# Misc.net
KiCad netlist of a schematic drawn in Altium Designer
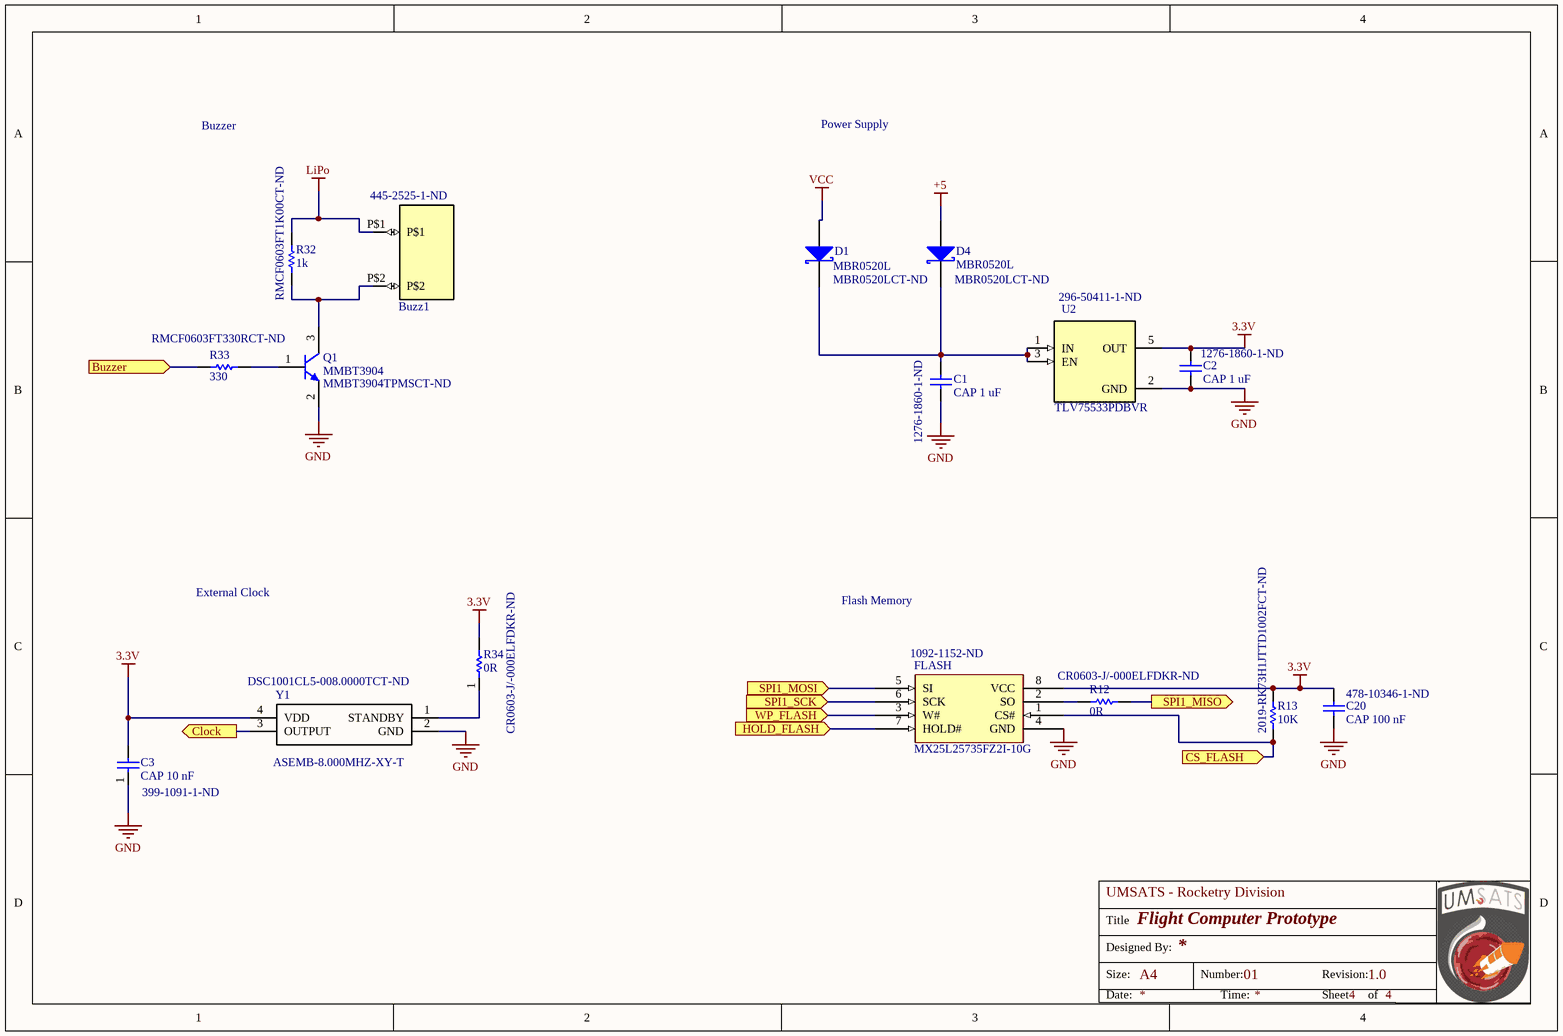
[diagram p0: Misc.SchDoc]

(export (version "E")
  (design (tool "Eeschema 10.0.6"))
  (components
    (comp (ref "Buzz1")
      (value "PS1240P02BT")
      (footprint "*PS1240P02BT_PS1240P02BT(Primary)")
      (description "Audio Buzzer Piezo 30Vo-p 3Vo-p 70dBA Pin Through Hole T/R")
      (fields (field (name "MF") "TDK") (field (name "SUPPLIER PART NUMBER 1") "445-2525-1-ND"))
      (libsource (lib "PS1240P02BT") (part "PS1240P02BT"))
    )
    (comp (ref "C1")
      (value "CAP 1 uF")
      (footprint "CL10A105KB8NNNC")
      (description "Capacitor")
      (fields
        (field (name "SUPPLIER PART NUMBER 1") "1276-1860-1-ND")
        (field (name "PUBLISHER") "Altium Limited")
      )
      (libsource (lib "Miscellaneous Devices") (part "Cap"))
    )
    (comp (ref "C2")
      (value "CAP 1 uF")
      (footprint "CL10A105KB8NNNC")
      (description "Capacitor")
      (fields
        (field (name "SUPPLIER PART NUMBER 1") "1276-1860-1-ND")
        (field (name "PUBLISHER") "Altium Limited")
      )
      (libsource (lib "Miscellaneous Devices") (part "Cap"))
    )
    (comp (ref "C3")
      (value "CAP 10 nF")
      (footprint "06035C104KAT4A")
      (description "Capacitor")
      (fields
        (field (name "SUPPLIER PART NUMBER 1") "399-1091-1-ND")
        (field (name "PUBLISHER") "Altium Limited")
      )
      (libsource (lib "") (part "Cap_1"))
    )
    (comp (ref "C20")
      (value "CAP 100 nF")
      (footprint "06035C104KAT4A")
      (description "Capacitor")
      (fields
        (field (name "SUPPLIER PART NUMBER 1") "478-10346-1-ND")
        (field (name "PUBLISHER") "Altium Limited")
      )
      (libsource (lib "Miscellaneous Devices") (part "Cap"))
    )
    (comp (ref "D1")
      (value "MBR0520L")
      (footprint "ON_Semi_CASE_425_0")
      (description "Schottky Diode")
      (fields
        (field (name "MANUFACTURER") "ON Semiconductor / Fairchild")
        (field (name "SUPPLIER PART NUMBER 1") "MBR0520LCT-ND")
      )
      (libsource (lib "MBR0520L") (part "MBR0520L"))
    )
    (comp (ref "D4")
      (value "MBR0520L")
      (footprint "ON_Semi_CASE_425_0")
      (description "Schottky Diode")
      (fields
        (field (name "MANUFACTURER") "ON Semiconductor / Fairchild")
        (field (name "SUPPLIER PART NUMBER 1") "MBR0520LCT-ND")
      )
      (libsource (lib "MBR0520L") (part "MBR0520L"))
    )
    (comp (ref "FLASH")
      (value "MX25L25735FZ2I-10G")
      (footprint "MX25L25735F:SON127P800X80_HS-9N")
      (description "MX25L25735F 256 Mb Flash Memory")
      (fields (field (name "SUPPLIER PART NUMBER 1") "1092-1152-ND"))
      (libsource (lib "S25FL064P_FlashMemory") (part "S25FL064P"))
    )
    (comp (ref "Q1")
      (value "MMBT3904")
      (footprint "FAIR-SOT23-3_V")
      (description "NPN General Purpose Amplifier, 40 V, 0.2 A, -55 to 150 degC, 3-Pin SOT23, RoHS, Tape and Reel")
      (fields (field (name "TOLERANCE") "30ppm") (field (name "SUPPLIER PART NUMBER 1") "MMBT3904TPMSCT-ND"))
      (libsource (lib "Altium Content Vault") (part "BJT-NPN-BEC-3"))
    )
    (comp (ref "R12")
      (value "0R")
      (footprint "CR0603-J/-000ELF")
      (description "Resistor")
      (fields
        (field (name "SUPPLIER PART NUMBER 1") "CR0603-J/-000ELFDKR-ND")
        (field (name "PUBLISHER") "Altium Limited")
      )
      (libsource (lib "Miscellaneous Devices") (part "Res1"))
    )
    (comp (ref "R13")
      (value "10K")
      (footprint "RK73H1JTTD1002F")
      (description "Resistor")
      (fields
        (field (name "SUPPLIER PART NUMBER 1") "2019-RK73H1JTTD1002FCT-ND")
        (field (name "PUBLISHER") "Altium Limited")
      )
      (libsource (lib "Miscellaneous Devices") (part "Res1"))
    )
    (comp (ref "R32")
      (value "1k")
      (footprint "CR0603-J/-000ELF")
      (description "Resistor")
      (fields
        (field (name "SUPPLIER PART NUMBER 1") "RMCF0603FT1K00CT-ND")
        (field (name "PUBLISHER") "Altium Limited")
      )
      (libsource (lib "Miscellaneous Devices") (part "Res1"))
    )
    (comp (ref "R33")
      (value "330")
      (footprint "CR0603-J/-000ELF")
      (description "Resistor")
      (fields
        (field (name "SUPPLIER PART NUMBER 1") "RMCF0603FT330RCT-ND")
        (field (name "PUBLISHER") "Altium Limited")
      )
      (libsource (lib "Miscellaneous Devices") (part "Res1"))
    )
    (comp (ref "R34")
      (value "0R")
      (footprint "CR0603-J/-000ELF")
      (description "Resistor")
      (fields
        (field (name "SUPPLIER PART NUMBER 1") "CR0603-J/-000ELFDKR-ND")
        (field (name "PUBLISHER") "Altium Limited")
      )
      (libsource (lib "") (part "Res1_1"))
    )
    (comp (ref "U2")
      (value "TLV75533PDBVR")
      (footprint "SOT95P280X145-5N")
      (description "500mA Low-IQ Small-Size Low-Dropout _LDO_ Regulator 5-SOT-23 -40 to 125")
      (fields
        (field (name "MF") "Texas Instruments")
        (field (name "SUPPLIER PART NUMBER 1") "296-50411-1-ND")
      )
      (libsource (lib "TLV75533PDBVR") (part "TLV75533PDBVR"))
    )
    (comp (ref "Y1")
      (value "ASEMB-8.000MHZ-XY-T")
      (footprint "SamacSys:ASEMB")
      (description "Crystal or Oscillator")
      (fields
        (field (name "MOUSER PART NUMBER") "815-ASEMB-8-XY-T")
        (field (name "SUPPLIER PART NUMBER 1") "DSC1001CL5-008.0000TCT-ND")
      )
      (libsource (lib "*") (part "ASEMB-8.000MHZ-XY-T"))
    )
  )
  (nets
    (net (code "1") (name "+5") (class "Default")
      (node (ref "D4") (pin "1") (pinfunction "A_1") (pintype "passive"))
    )
    (net (code "2") (name "/Buzzer") (class "Default")
      (node (ref "R33") (pin "1") (pinfunction "1_1") (pintype "passive"))
    )
    (net (code "3") (name "/CS_FLASH") (class "Default")
      (node (ref "FLASH") (pin "1") (pinfunction "CS#_1") (pintype "input"))
      (node (ref "R13") (pin "1") (pinfunction "1_1") (pintype "passive"))
    )
    (net (code "4") (name "/Clock") (class "Default")
      (node (ref "Y1") (pin "3") (pinfunction "OUTPUT_3") (pintype "passive"))
    )
    (net (code "5") (name "/HOLD_FLASH") (class "Default")
      (node (ref "FLASH") (pin "7") (pinfunction "HOLD#_7") (pintype "input"))
    )
    (net (code "6") (name "/SPI1_MISO") (class "Default")
      (node (ref "R12") (pin "2") (pinfunction "2_2") (pintype "passive"))
    )
    (net (code "7") (name "/SPI1_MOSI") (class "Default")
      (node (ref "FLASH") (pin "5") (pinfunction "SI_5") (pintype "input"))
    )
    (net (code "8") (name "/SPI1_SCK") (class "Default")
      (node (ref "FLASH") (pin "6") (pinfunction "SCK_6") (pintype "input"))
    )
    (net (code "9") (name "/WP_FLASH") (class "Default")
      (node (ref "FLASH") (pin "3") (pinfunction "W#_3") (pintype "input"))
    )
    (net (code "10") (name "3.3V") (class "Default")
      (node (ref "C2") (pin "1") (pinfunction "1_1") (pintype "passive"))
      (node (ref "C20") (pin "1") (pinfunction "1_1") (pintype "passive"))
      (node (ref "C3") (pin "2") (pinfunction "2_2") (pintype "passive"))
      (node (ref "FLASH") (pin "8") (pinfunction "VCC_8") (pintype "power_in"))
      (node (ref "R13") (pin "2") (pinfunction "2_2") (pintype "passive"))
      (node (ref "R34") (pin "2") (pinfunction "2_2") (pintype "passive"))
      (node (ref "U2") (pin "5") (pinfunction "OUT_5") (pintype "power_in"))
      (node (ref "Y1") (pin "4") (pinfunction "VDD_4") (pintype "passive"))
    )
    (net (code "11") (name "GND") (class "Default")
      (node (ref "C1") (pin "2") (pinfunction "2_2") (pintype "passive"))
      (node (ref "C2") (pin "2") (pinfunction "2_2") (pintype "passive"))
      (node (ref "C20") (pin "2") (pinfunction "2_2") (pintype "passive"))
      (node (ref "C3") (pin "1") (pinfunction "1_1") (pintype "passive"))
      (node (ref "FLASH") (pin "4") (pinfunction "GND_4") (pintype "power_in"))
      (node (ref "Q1") (pin "2") (pinfunction "E_2") (pintype "passive"))
      (node (ref "U2") (pin "2") (pinfunction "GND_2") (pintype "power_in"))
      (node (ref "Y1") (pin "2") (pinfunction "GND_2") (pintype "passive"))
    )
    (net (code "12") (name "LiPo") (class "Default")
      (node (ref "Buzz1") (pin "P$1") (pinfunction "P$1_P$1") (pintype "bidirectional"))
      (node (ref "R32") (pin "2") (pinfunction "2_2") (pintype "passive"))
    )
    (net (code "13") (name "Net-(D1-K)") (class "Default")
      (node (ref "C1") (pin "1") (pinfunction "1_1") (pintype "passive"))
      (node (ref "D1") (pin "2") (pinfunction "K_2") (pintype "passive"))
      (node (ref "D4") (pin "2") (pinfunction "K_2") (pintype "passive"))
      (node (ref "U2") (pin "1") (pinfunction "IN_1") (pintype "input"))
      (node (ref "U2") (pin "3") (pinfunction "EN_3") (pintype "input"))
    )
    (net (code "14") (name "Net-(FLASH-SO)") (class "Default")
      (node (ref "FLASH") (pin "2") (pinfunction "SO_2") (pintype "power_in"))
      (node (ref "R12") (pin "1") (pinfunction "1_1") (pintype "passive"))
    )
    (net (code "15") (name "Net-(Q1-B)") (class "Default")
      (node (ref "Q1") (pin "1") (pinfunction "B_1") (pintype "passive"))
      (node (ref "R33") (pin "2") (pinfunction "2_2") (pintype "passive"))
    )
    (net (code "16") (name "Net-(Q1-C)") (class "Default")
      (node (ref "Buzz1") (pin "P$2") (pinfunction "P$2_P$2") (pintype "bidirectional"))
      (node (ref "Q1") (pin "3") (pinfunction "C_3") (pintype "passive"))
      (node (ref "R32") (pin "1") (pinfunction "1_1") (pintype "passive"))
    )
    (net (code "17") (name "Net-(Y1-STANDBY)") (class "Default")
      (node (ref "R34") (pin "1") (pinfunction "1_1") (pintype "passive"))
      (node (ref "Y1") (pin "1") (pinfunction "STANDBY_1") (pintype "passive"))
    )
    (net (code "18") (name "VCC") (class "Default")
      (node (ref "D1") (pin "1") (pinfunction "A_1") (pintype "passive"))
    )
  )
)
